# wiring_harnesses.net
KiCad netlist of a schematic drawn in EAGLE
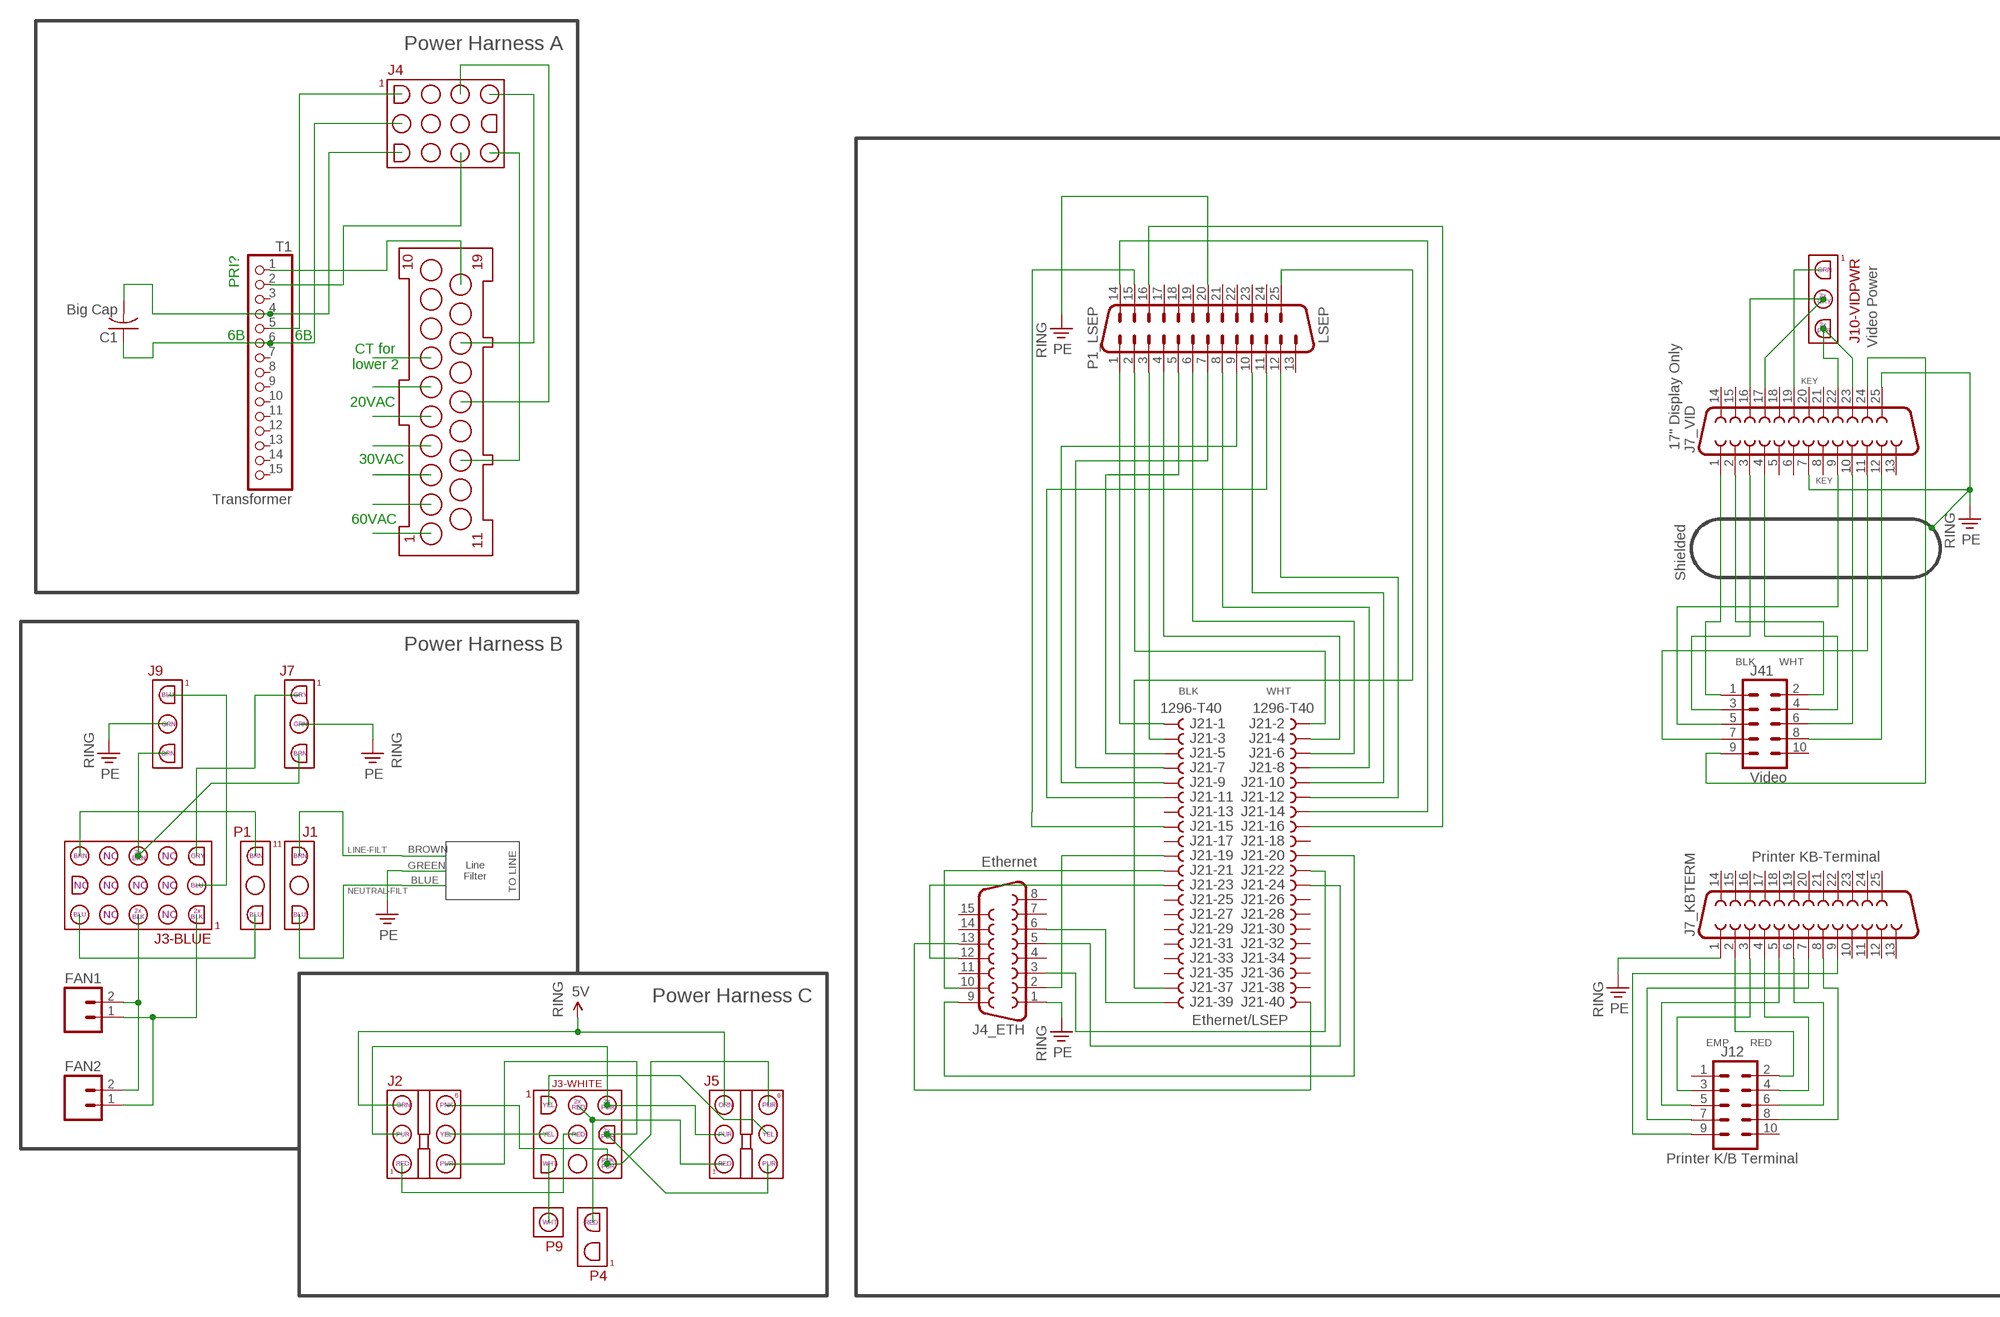
[diagram p0: schematic, sheet 1, part 1 of 2]
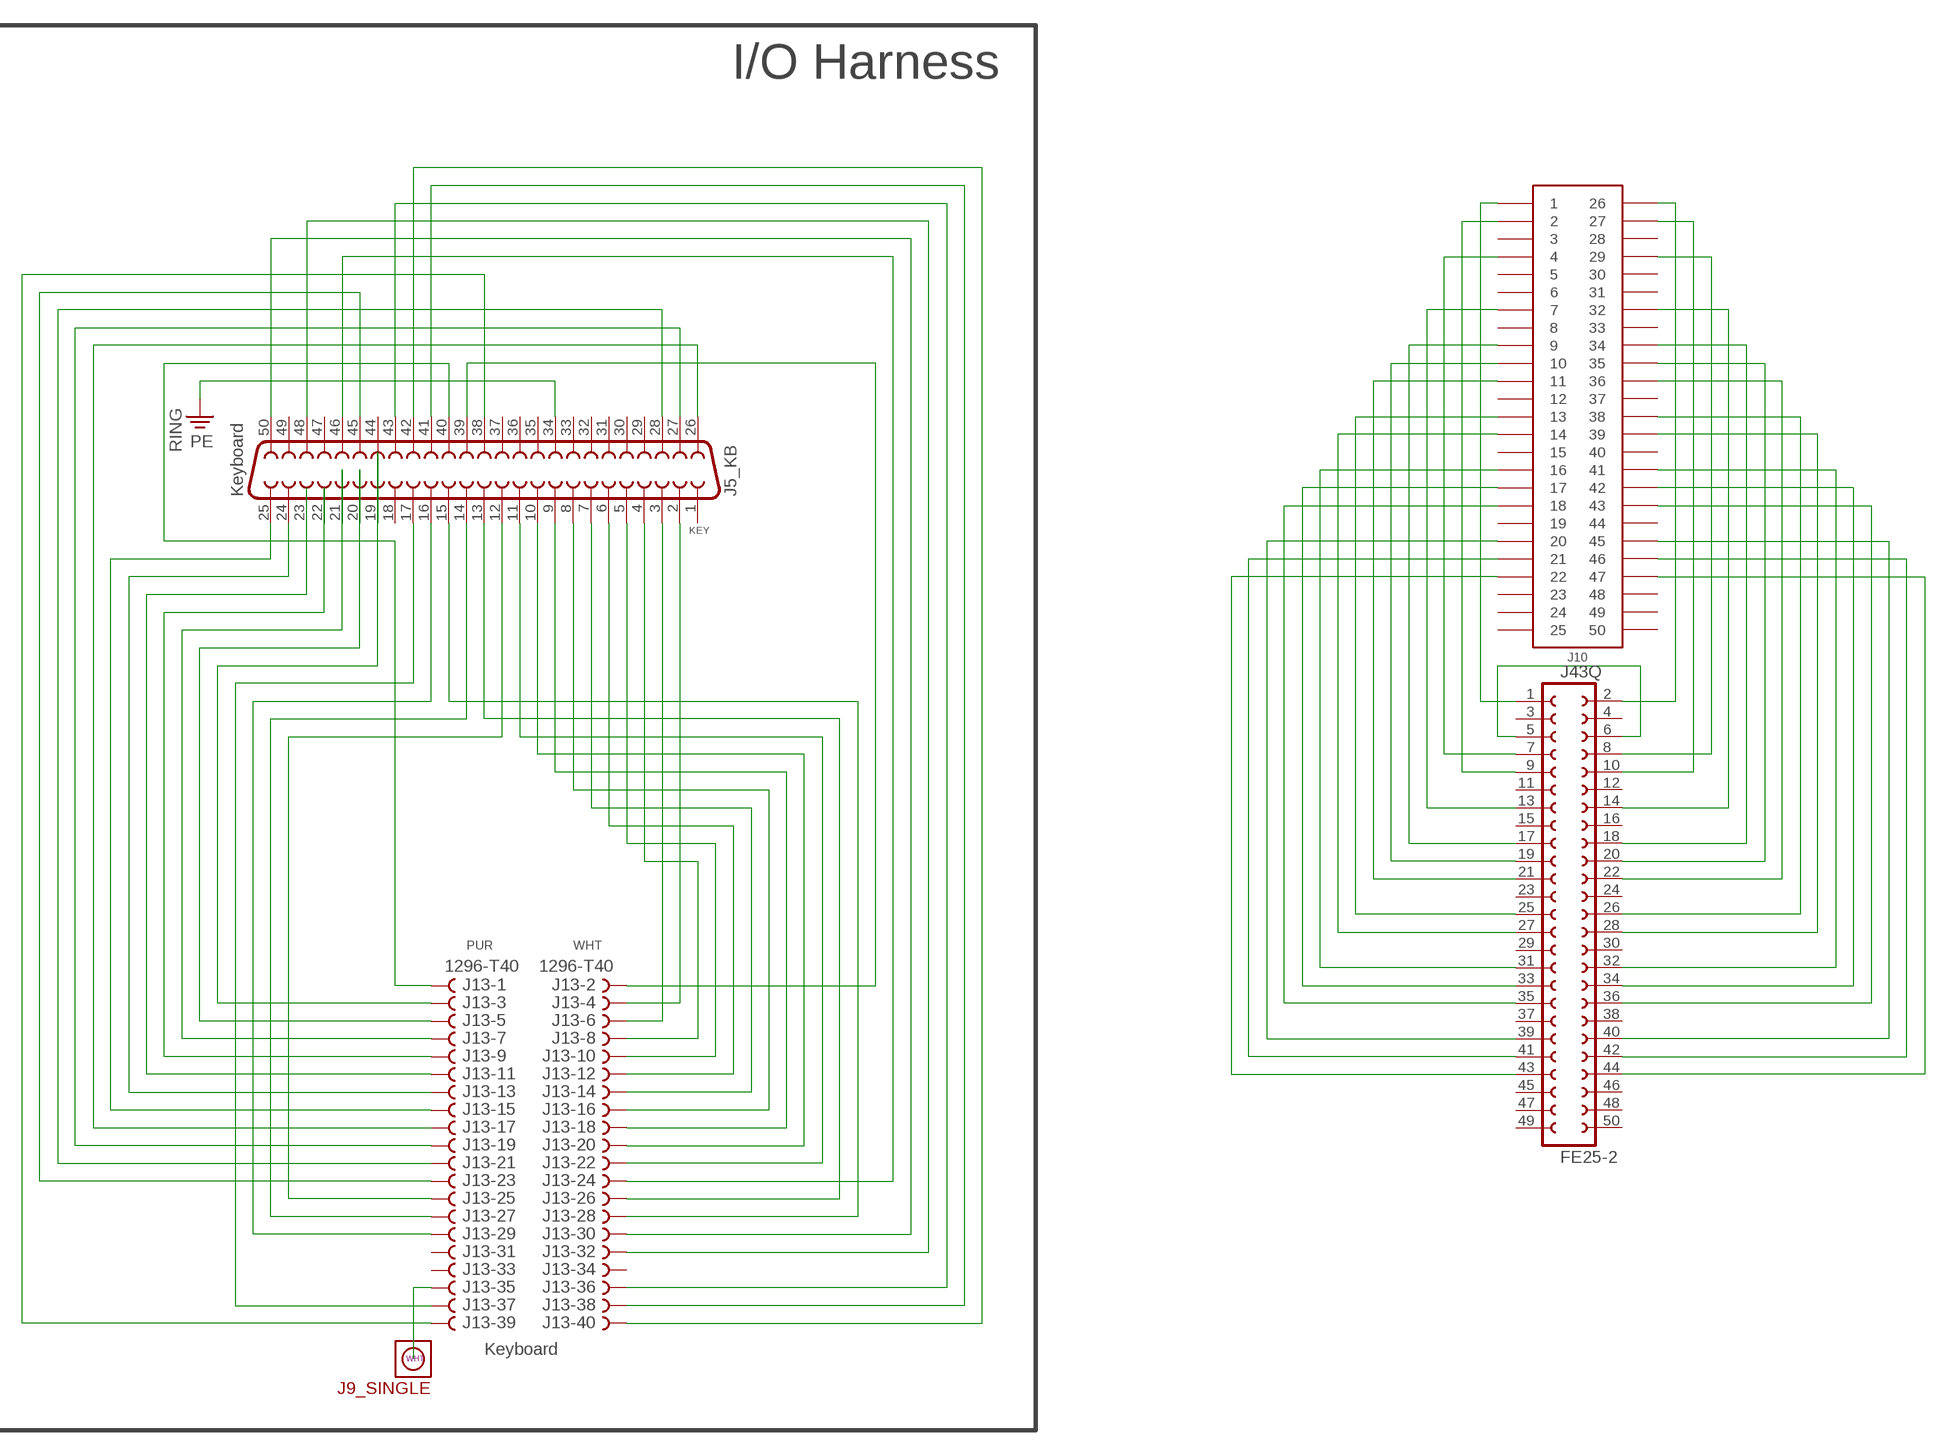
[diagram p1: schematic, sheet 1, part 2 of 2]

(export (version "E")
  (design (tool "Eeschema 10.0.6"))
  (components
    (comp (ref "C1")
      (value "Big Cap")
      (footprint "eagle-import:C275-173X316")
      (libsource (lib "eagle-import") (part "C-US275-173X316"))
    )
    (comp (ref "FAN1")
      (value "M02POGO_PIN_HOLES_ONLY")
      (footprint "eagle-import:1X02_PP_HOLES_ONLY")
      (libsource (lib "eagle-import") (part "M02POGO_PIN_HOLES_ONLY"))
    )
    (comp (ref "FAN2")
      (value "M02POGO_PIN_HOLES_ONLY")
      (footprint "eagle-import:1X02_PP_HOLES_ONLY")
      (libsource (lib "eagle-import") (part "M02POGO_PIN_HOLES_ONLY"))
    )
    (comp (ref "J1")
      (value "MOLEX-MLX3X1")
      (footprint "eagle-import:MOLEX-MLX3X1")
      (libsource (lib "eagle-import") (part "MOLEX-MLX3X1"))
    )
    (comp (ref "J2")
      (value "AMP-MATENLOK-3X2")
      (footprint "eagle-import:MATENLOK-3X2")
      (libsource (lib "eagle-import") (part "AMP-MATENLOK-3X2"))
    )
    (comp (ref "J3-BLUE")
      (value "MOLEX-MLX3X5")
      (footprint "eagle-import:MOLEX-MLX3X5")
      (libsource (lib "eagle-import") (part "MOLEX-MLX3X5"))
    )
    (comp (ref "J3-WHITE")
      (value "MOLEX-MLX3X3")
      (footprint "eagle-import:MOLEX-MLX3X3")
      (libsource (lib "eagle-import") (part "MOLEX-MLX3X3"))
    )
    (comp (ref "J4")
      (value "MOLEX-MLX3X4")
      (footprint "eagle-import:MOLEX-MLX3X4")
      (libsource (lib "eagle-import") (part "MOLEX-MLX3X4"))
    )
    (comp (ref "J4_ETH")
      (value "Ethernet")
      (footprint "eagle-import:F15D")
      (libsource (lib "eagle-import") (part "F15D"))
    )
    (comp (ref "J5")
      (value "AMP-MATENLOK-3X2")
      (footprint "eagle-import:MATENLOK-3X2")
      (libsource (lib "eagle-import") (part "AMP-MATENLOK-3X2"))
    )
    (comp (ref "J5_KB")
      (value "Keyboard")
      (footprint "eagle-import:F50VP")
      (libsource (lib "eagle-import") (part "F50VP"))
    )
    (comp (ref "J7")
      (value "MOLEX-MLX3X1")
      (footprint "eagle-import:MOLEX-MLX3X1")
      (libsource (lib "eagle-import") (part "MOLEX-MLX3X1"))
    )
    (comp (ref "J7_KBTERM")
      (value "Printer KB-Terminal")
      (footprint "eagle-import:F25VP")
      (libsource (lib "eagle-import") (part "F25VP"))
    )
    (comp (ref "J7_VID")
      (value "17\" Display Only")
      (footprint "eagle-import:F25VP")
      (libsource (lib "eagle-import") (part "F25VP"))
    )
    (comp (ref "J9")
      (value "MOLEX-MLX3X1")
      (footprint "eagle-import:MOLEX-MLX3X1")
      (libsource (lib "eagle-import") (part "MOLEX-MLX3X1"))
    )
    (comp (ref "J9_SINGLE")
      (value "MOLEX-MLX1X1")
      (footprint "eagle-import:MOLEX-MLX1X1")
      (libsource (lib "eagle-import") (part "MOLEX-MLX1X1"))
    )
    (comp (ref "J10")
      (value "EDGECON-F-0.1-50")
      (footprint "eagle-import:EDGECON-M-0.1-50")
      (libsource (lib "eagle-import") (part "EDGECON-F-0.1-50"))
    )
    (comp (ref "J10-VIDPWR")
      (value "Video Power")
      (footprint "eagle-import:MOLEX-MLX3X1")
      (libsource (lib "eagle-import") (part "MOLEX-MLX3X1"))
    )
    (comp (ref "J12")
      (value "Printer K/B Terminal")
      (footprint "eagle-import:2X5_NOSILK")
      (libsource (lib "eagle-import") (part "M05X2NO_SILK"))
    )
    (comp (ref "J13")
      (value "1296-T40")
      (footprint "eagle-import:1296-40")
      (libsource (lib "eagle-import") (part "1296-T40"))
    )
    (comp (ref "J21")
      (value "1296-T40")
      (footprint "eagle-import:1296-40")
      (libsource (lib "eagle-import") (part "1296-T40"))
    )
    (comp (ref "J41")
      (value "Video")
      (footprint "eagle-import:2X5_NOSILK")
      (libsource (lib "eagle-import") (part "M05X2NO_SILK"))
    )
    (comp (ref "J43Q")
      (value "FE25-2")
      (footprint "eagle-import:MA25-2")
      (libsource (lib "eagle-import") (part "FE25-2"))
    )
    (comp (ref "P1")
      (value "MOLEX-MLX3X1")
      (footprint "eagle-import:MOLEX-MLX3X1")
      (libsource (lib "eagle-import") (part "MOLEX-MLX3X1"))
    )
    (comp (ref "P1_LSEP")
      (value "LSEP")
      (footprint "eagle-import:M25VP")
      (libsource (lib "eagle-import") (part "DB25VP"))
    )
    (comp (ref "P4")
      (value "MOLEX-MLX2X1")
      (footprint "eagle-import:MOLEX-MLX2X1")
      (libsource (lib "eagle-import") (part "MOLEX-MLX2X1"))
    )
    (comp (ref "P9")
      (value "MOLEX-MLX1X1")
      (footprint "eagle-import:MOLEX-MLX1X1")
      (libsource (lib "eagle-import") (part "MOLEX-MLX1X1"))
    )
    (comp (ref "PSUCONN")
      (value "AMP-METRIMATE-19")
      (footprint "eagle-import:AMP-METRIMATE-19")
      (libsource (lib "eagle-import") (part "AMP-METRIMATE-19"))
    )
    (comp (ref "T1")
      (value "Transformer")
      (footprint "eagle-import:1X15")
      (libsource (lib "eagle-import") (part "PINHD-1X15"))
    )
  )
  (nets
    (net (code "1") (name "/LINE-FILT") (class "Default")
      (node (ref "J1") (pin "1") (pinfunction "1_1") (pintype "passive"))
    )
    (net (code "2") (name "/NEUTRAL-FILT") (class "Default")
      (node (ref "J1") (pin "3") (pinfunction "3_3") (pintype "passive"))
    )
    (net (code "3") (name "5V") (class "Default")
      (node (ref "J2") (pin "5") (pinfunction "5_5") (pintype "passive"))
      (node (ref "J5") (pin "5") (pinfunction "5_5") (pintype "passive"))
    )
    (net (code "4") (name "Net-(C1-Pad1)") (class "Default")
      (node (ref "C1") (pin "1") (pinfunction "1_1") (pintype "passive"))
      (node (ref "T1") (pin "6") (pinfunction "6_6") (pintype "passive"))
    )
    (net (code "5") (name "Net-(C1-Pad2)") (class "Default")
      (node (ref "C1") (pin "2") (pinfunction "2_2") (pintype "passive"))
      (node (ref "T1") (pin "4") (pinfunction "4_4") (pintype "passive"))
    )
    (net (code "6") (name "Net-(J2-Pad1)") (class "Default")
      (node (ref "J2") (pin "1") (pinfunction "1_1") (pintype "passive"))
      (node (ref "J3-WHITE") (pin "5") (pinfunction "5_5") (pintype "passive"))
    )
    (net (code "7") (name "Net-(J2-Pad2)") (class "Default")
      (node (ref "J2") (pin "2") (pinfunction "2_2") (pintype "passive"))
      (node (ref "J3-WHITE") (pin "8") (pinfunction "8_8") (pintype "passive"))
      (node (ref "J5") (pin "2") (pinfunction "2_2") (pintype "passive"))
    )
    (net (code "8") (name "Net-(J2-Pad3)") (class "Default")
      (node (ref "J2") (pin "3") (pinfunction "3_3") (pintype "passive"))
      (node (ref "J3-WHITE") (pin "7") (pinfunction "7_7") (pintype "passive"))
      (node (ref "J5") (pin "3") (pinfunction "3_3") (pintype "passive"))
    )
    (net (code "9") (name "Net-(J2-Pad4)") (class "Default")
      (node (ref "J2") (pin "4") (pinfunction "4_4") (pintype "passive"))
      (node (ref "J3-WHITE") (pin "2") (pinfunction "2_2") (pintype "passive"))
    )
    (net (code "10") (name "Net-(J2-Pad6)") (class "Default")
      (node (ref "J2") (pin "6") (pinfunction "6_6") (pintype "passive"))
      (node (ref "J3-WHITE") (pin "9") (pinfunction "9_9") (pintype "passive"))
      (node (ref "J5") (pin "6") (pinfunction "6_6") (pintype "passive"))
    )
    (net (code "11") (name "Net-(J3-BLUE-1)") (class "Default")
      (node (ref "FAN1") (pin "1") (pinfunction "1_1") (pintype "passive"))
      (node (ref "FAN2") (pin "1") (pinfunction "1_1") (pintype "passive"))
      (node (ref "J3-BLUE") (pin "15") (pinfunction "1_15") (pintype "passive"))
    )
    (net (code "12") (name "Net-(J3-BLUE-2)") (class "Default")
      (node (ref "J3-BLUE") (pin "14") (pinfunction "2_14") (pintype "passive"))
      (node (ref "J9") (pin "1") (pinfunction "1_1") (pintype "passive"))
    )
    (net (code "13") (name "Net-(J3-BLUE-3)") (class "Default")
      (node (ref "J3-BLUE") (pin "13") (pinfunction "3_13") (pintype "passive"))
      (node (ref "J7") (pin "1") (pinfunction "1_1") (pintype "passive"))
    )
    (net (code "14") (name "Net-(J3-BLUE-7)") (class "Default")
      (node (ref "FAN1") (pin "2") (pinfunction "2_2") (pintype "passive"))
      (node (ref "FAN2") (pin "2") (pinfunction "2_2") (pintype "passive"))
      (node (ref "J3-BLUE") (pin "9") (pinfunction "7_9") (pintype "passive"))
    )
    (net (code "15") (name "Net-(J3-BLUE-9)") (class "Default")
      (node (ref "J3-BLUE") (pin "7") (pinfunction "9_7") (pintype "passive"))
      (node (ref "J7") (pin "3") (pinfunction "3_3") (pintype "passive"))
      (node (ref "J9") (pin "3") (pinfunction "3_3") (pintype "passive"))
    )
    (net (code "16") (name "Net-(J3-BLUE-13)") (class "Default")
      (node (ref "J3-BLUE") (pin "3") (pinfunction "13_3") (pintype "passive"))
      (node (ref "P1") (pin "3") (pinfunction "3_3") (pintype "passive"))
    )
    (net (code "17") (name "Net-(J3-BLUE-15)") (class "Default")
      (node (ref "J3-BLUE") (pin "1") (pinfunction "15_1") (pintype "passive"))
      (node (ref "P1") (pin "1") (pinfunction "1_1") (pintype "passive"))
    )
    (net (code "18") (name "Net-(J3-WHITE-Pad1)") (class "Default")
      (node (ref "J3-WHITE") (pin "1") (pinfunction "1_1") (pintype "passive"))
      (node (ref "J5") (pin "4") (pinfunction "4_4") (pintype "passive"))
    )
    (net (code "19") (name "Net-(J3-WHITE-Pad3)") (class "Default")
      (node (ref "J3-WHITE") (pin "3") (pinfunction "3_3") (pintype "passive"))
      (node (ref "P9") (pin "1") (pinfunction "1_1") (pintype "passive"))
    )
    (net (code "20") (name "Net-(J3-WHITE-Pad4)") (class "Default")
      (node (ref "J3-WHITE") (pin "4") (pinfunction "4_4") (pintype "passive"))
      (node (ref "J5") (pin "1") (pinfunction "1_1") (pintype "passive"))
      (node (ref "P4") (pin "2") (pinfunction "2_2") (pintype "passive"))
    )
    (net (code "21") (name "Net-(J10-Pad1)") (class "Default")
      (node (ref "J10") (pin "1") (pinfunction "1_1") (pintype "bidirectional"))
      (node (ref "J43Q") (pin "1") (pinfunction "1_1") (pintype "passive"))
    )
    (net (code "22") (name "Net-(J10-Pad2)") (class "Default")
      (node (ref "J10") (pin "2") (pinfunction "2_2") (pintype "bidirectional"))
      (node (ref "J43Q") (pin "9") (pinfunction "9_9") (pintype "passive"))
    )
    (net (code "23") (name "Net-(J10-Pad4)") (class "Default")
      (node (ref "J10") (pin "4") (pinfunction "4_4") (pintype "bidirectional"))
      (node (ref "J43Q") (pin "7") (pinfunction "7_7") (pintype "passive"))
    )
    (net (code "24") (name "Net-(J10-Pad7)") (class "Default")
      (node (ref "J10") (pin "7") (pinfunction "7_7") (pintype "bidirectional"))
      (node (ref "J43Q") (pin "13") (pinfunction "13_13") (pintype "passive"))
    )
    (net (code "25") (name "Net-(J10-Pad9)") (class "Default")
      (node (ref "J10") (pin "9") (pinfunction "9_9") (pintype "bidirectional"))
      (node (ref "J43Q") (pin "17") (pinfunction "17_17") (pintype "passive"))
    )
    (net (code "26") (name "Net-(J10-Pad10)") (class "Default")
      (node (ref "J10") (pin "10") (pinfunction "10_10") (pintype "bidirectional"))
      (node (ref "J43Q") (pin "19") (pinfunction "19_19") (pintype "passive"))
    )
    (net (code "27") (name "Net-(J10-Pad11)") (class "Default")
      (node (ref "J10") (pin "11") (pinfunction "11_11") (pintype "bidirectional"))
      (node (ref "J43Q") (pin "21") (pinfunction "21_21") (pintype "passive"))
    )
    (net (code "28") (name "Net-(J10-Pad13)") (class "Default")
      (node (ref "J10") (pin "13") (pinfunction "13_13") (pintype "bidirectional"))
      (node (ref "J43Q") (pin "25") (pinfunction "25_25") (pintype "passive"))
    )
    (net (code "29") (name "Net-(J10-Pad14)") (class "Default")
      (node (ref "J10") (pin "14") (pinfunction "14_14") (pintype "bidirectional"))
      (node (ref "J43Q") (pin "27") (pinfunction "27_27") (pintype "passive"))
    )
    (net (code "30") (name "Net-(J10-Pad16)") (class "Default")
      (node (ref "J10") (pin "16") (pinfunction "16_16") (pintype "bidirectional"))
      (node (ref "J43Q") (pin "31") (pinfunction "31_31") (pintype "passive"))
    )
    (net (code "31") (name "Net-(J10-Pad17)") (class "Default")
      (node (ref "J10") (pin "17") (pinfunction "17_17") (pintype "bidirectional"))
      (node (ref "J43Q") (pin "33") (pinfunction "33_33") (pintype "passive"))
    )
    (net (code "32") (name "Net-(J10-Pad18)") (class "Default")
      (node (ref "J10") (pin "18") (pinfunction "18_18") (pintype "bidirectional"))
      (node (ref "J43Q") (pin "35") (pinfunction "35_35") (pintype "passive"))
    )
    (net (code "33") (name "Net-(J10-Pad20)") (class "Default")
      (node (ref "J10") (pin "20") (pinfunction "20_20") (pintype "bidirectional"))
      (node (ref "J43Q") (pin "39") (pinfunction "39_39") (pintype "passive"))
    )
    (net (code "34") (name "Net-(J10-Pad21)") (class "Default")
      (node (ref "J10") (pin "21") (pinfunction "21_21") (pintype "bidirectional"))
      (node (ref "J43Q") (pin "41") (pinfunction "41_41") (pintype "passive"))
    )
    (net (code "35") (name "Net-(J10-Pad22)") (class "Default")
      (node (ref "J10") (pin "22") (pinfunction "22_22") (pintype "bidirectional"))
      (node (ref "J43Q") (pin "43") (pinfunction "43_43") (pintype "passive"))
    )
    (net (code "36") (name "Net-(J10-Pad26)") (class "Default")
      (node (ref "J10") (pin "26") (pinfunction "26_26") (pintype "bidirectional"))
      (node (ref "J43Q") (pin "2") (pinfunction "2_2") (pintype "passive"))
    )
    (net (code "37") (name "Net-(J10-Pad27)") (class "Default")
      (node (ref "J10") (pin "27") (pinfunction "27_27") (pintype "bidirectional"))
      (node (ref "J43Q") (pin "10") (pinfunction "10_10") (pintype "passive"))
    )
    (net (code "38") (name "Net-(J10-Pad29)") (class "Default")
      (node (ref "J10") (pin "29") (pinfunction "29_29") (pintype "bidirectional"))
      (node (ref "J43Q") (pin "8") (pinfunction "8_8") (pintype "passive"))
    )
    (net (code "39") (name "Net-(J10-Pad32)") (class "Default")
      (node (ref "J10") (pin "32") (pinfunction "32_32") (pintype "bidirectional"))
      (node (ref "J43Q") (pin "14") (pinfunction "14_14") (pintype "passive"))
    )
    (net (code "40") (name "Net-(J10-Pad34)") (class "Default")
      (node (ref "J10") (pin "34") (pinfunction "34_34") (pintype "bidirectional"))
      (node (ref "J43Q") (pin "18") (pinfunction "18_18") (pintype "passive"))
    )
    (net (code "41") (name "Net-(J10-Pad35)") (class "Default")
      (node (ref "J10") (pin "35") (pinfunction "35_35") (pintype "bidirectional"))
      (node (ref "J43Q") (pin "20") (pinfunction "20_20") (pintype "passive"))
    )
    (net (code "42") (name "Net-(J10-Pad36)") (class "Default")
      (node (ref "J10") (pin "36") (pinfunction "36_36") (pintype "bidirectional"))
      (node (ref "J43Q") (pin "22") (pinfunction "22_22") (pintype "passive"))
    )
    (net (code "43") (name "Net-(J10-Pad38)") (class "Default")
      (node (ref "J10") (pin "38") (pinfunction "38_38") (pintype "bidirectional"))
      (node (ref "J43Q") (pin "26") (pinfunction "26_26") (pintype "passive"))
    )
    (net (code "44") (name "Net-(J10-Pad39)") (class "Default")
      (node (ref "J10") (pin "39") (pinfunction "39_39") (pintype "bidirectional"))
      (node (ref "J43Q") (pin "28") (pinfunction "28_28") (pintype "passive"))
    )
    (net (code "45") (name "Net-(J10-Pad41)") (class "Default")
      (node (ref "J10") (pin "41") (pinfunction "41_41") (pintype "bidirectional"))
      (node (ref "J43Q") (pin "32") (pinfunction "32_32") (pintype "passive"))
    )
    (net (code "46") (name "Net-(J10-Pad42)") (class "Default")
      (node (ref "J10") (pin "42") (pinfunction "42_42") (pintype "bidirectional"))
      (node (ref "J43Q") (pin "34") (pinfunction "34_34") (pintype "passive"))
    )
    (net (code "47") (name "Net-(J10-Pad43)") (class "Default")
      (node (ref "J10") (pin "43") (pinfunction "43_43") (pintype "bidirectional"))
      (node (ref "J43Q") (pin "36") (pinfunction "36_36") (pintype "passive"))
    )
    (net (code "48") (name "Net-(J10-Pad45)") (class "Default")
      (node (ref "J10") (pin "45") (pinfunction "45_45") (pintype "bidirectional"))
      (node (ref "J43Q") (pin "40") (pinfunction "40_40") (pintype "passive"))
    )
    (net (code "49") (name "Net-(J10-Pad46)") (class "Default")
      (node (ref "J10") (pin "46") (pinfunction "46_46") (pintype "bidirectional"))
      (node (ref "J43Q") (pin "42") (pinfunction "42_42") (pintype "passive"))
    )
    (net (code "50") (name "Net-(J10-Pad47)") (class "Default")
      (node (ref "J10") (pin "47") (pinfunction "47_47") (pintype "bidirectional"))
      (node (ref "J43Q") (pin "44") (pinfunction "44_44") (pintype "passive"))
    )
    (net (code "51") (name "Net-(J10-VIDPWR-Pad1)") (class "Default")
      (node (ref "J10-VIDPWR") (pin "1") (pinfunction "1_1") (pintype "passive"))
      (node (ref "J7_VID") (pin "19") (pinfunction "19_19") (pintype "passive"))
    )
    (net (code "52") (name "Net-(J10-VIDPWR-Pad2)") (class "Default")
      (node (ref "J10-VIDPWR") (pin "2") (pinfunction "2_2") (pintype "passive"))
      (node (ref "J7_VID") (pin "16") (pinfunction "16_16") (pintype "passive"))
      (node (ref "J7_VID") (pin "17") (pinfunction "17_17") (pintype "passive"))
    )
    (net (code "53") (name "Net-(J10-VIDPWR-Pad3)") (class "Default")
      (node (ref "J10-VIDPWR") (pin "3") (pinfunction "3_3") (pintype "passive"))
      (node (ref "J7_VID") (pin "22") (pinfunction "22_22") (pintype "passive"))
      (node (ref "J7_VID") (pin "23") (pinfunction "23_23") (pintype "passive"))
    )
    (net (code "54") (name "Net-(J12-Pad2)") (class "Default")
      (node (ref "J12") (pin "2") (pinfunction "2_2") (pintype "passive"))
      (node (ref "J7_KBTERM") (pin "2") (pinfunction "2_2") (pintype "passive"))
    )
    (net (code "55") (name "Net-(J12-Pad3)") (class "Default")
      (node (ref "J12") (pin "3") (pinfunction "3_3") (pintype "passive"))
      (node (ref "J7_KBTERM") (pin "3") (pinfunction "3_3") (pintype "passive"))
    )
    (net (code "56") (name "Net-(J12-Pad4)") (class "Default")
      (node (ref "J12") (pin "4") (pinfunction "4_4") (pintype "passive"))
      (node (ref "J7_KBTERM") (pin "4") (pinfunction "4_4") (pintype "passive"))
    )
    (net (code "57") (name "Net-(J12-Pad5)") (class "Default")
      (node (ref "J12") (pin "5") (pinfunction "5_5") (pintype "passive"))
      (node (ref "J7_KBTERM") (pin "5") (pinfunction "5_5") (pintype "passive"))
    )
    (net (code "58") (name "Net-(J12-Pad6)") (class "Default")
      (node (ref "J12") (pin "6") (pinfunction "6_6") (pintype "passive"))
      (node (ref "J7_KBTERM") (pin "6") (pinfunction "6_6") (pintype "passive"))
    )
    (net (code "59") (name "Net-(J12-Pad7)") (class "Default")
      (node (ref "J12") (pin "7") (pinfunction "7_7") (pintype "passive"))
      (node (ref "J7_KBTERM") (pin "7") (pinfunction "7_7") (pintype "passive"))
    )
    (net (code "60") (name "Net-(J12-Pad8)") (class "Default")
      (node (ref "J12") (pin "8") (pinfunction "8_8") (pintype "passive"))
      (node (ref "J7_KBTERM") (pin "8") (pinfunction "8_8") (pintype "passive"))
    )
    (net (code "61") (name "Net-(J12-Pad9)") (class "Default")
      (node (ref "J12") (pin "9") (pinfunction "9_9") (pintype "passive"))
      (node (ref "J7_KBTERM") (pin "9") (pinfunction "9_9") (pintype "passive"))
    )
    (net (code "62") (name "Net-(J13A-B)") (class "Default")
      (node (ref "J13") (pin "1") (pinfunction "B_1") (pintype "passive"))
      (node (ref "J5_KB") (pin "40") (pinfunction "40_40") (pintype "passive"))
    )
    (net (code "63") (name "Net-(J13AC-B)") (class "Default")
      (node (ref "J13") (pin "35") (pinfunction "B_35") (pintype "passive"))
      (node (ref "J9_SINGLE") (pin "1") (pinfunction "1_1") (pintype "passive"))
    )
    (net (code "64") (name "Net-(J13AD-B)") (class "Default")
      (node (ref "J13") (pin "36") (pinfunction "B_36") (pintype "passive"))
      (node (ref "J5_KB") (pin "43") (pinfunction "43_43") (pintype "passive"))
    )
    (net (code "65") (name "Net-(J13AE-B)") (class "Default")
      (node (ref "J13") (pin "37") (pinfunction "B_37") (pintype "passive"))
      (node (ref "J5_KB") (pin "17") (pinfunction "17_17") (pintype "passive"))
    )
    (net (code "66") (name "Net-(J13AF-B)") (class "Default")
      (node (ref "J13") (pin "38") (pinfunction "B_38") (pintype "passive"))
      (node (ref "J5_KB") (pin "41") (pinfunction "41_41") (pintype "passive"))
    )
    (net (code "67") (name "Net-(J13AG-B)") (class "Default")
      (node (ref "J13") (pin "39") (pinfunction "B_39") (pintype "passive"))
      (node (ref "J5_KB") (pin "38") (pinfunction "38_38") (pintype "passive"))
    )
    (net (code "68") (name "Net-(J13AH-B)") (class "Default")
      (node (ref "J13") (pin "4") (pinfunction "B_4") (pintype "passive"))
      (node (ref "J5_KB") (pin "2") (pinfunction "2_2") (pintype "passive"))
    )
    (net (code "69") (name "Net-(J13AI-B)") (class "Default")
      (node (ref "J13") (pin "40") (pinfunction "B_40") (pintype "passive"))
      (node (ref "J5_KB") (pin "42") (pinfunction "42_42") (pintype "passive"))
    )
    (net (code "70") (name "Net-(J13AJ-B)") (class "Default")
      (node (ref "J13") (pin "5") (pinfunction "B_5") (pintype "passive"))
      (node (ref "J5_KB") (pin "20") (pinfunction "20_20") (pintype "passive"))
    )
    (net (code "71") (name "Net-(J13AK-B)") (class "Default")
      (node (ref "J13") (pin "6") (pinfunction "B_6") (pintype "passive"))
      (node (ref "J5_KB") (pin "3") (pinfunction "3_3") (pintype "passive"))
    )
    (net (code "72") (name "Net-(J13AL-B)") (class "Default")
      (node (ref "J13") (pin "7") (pinfunction "B_7") (pintype "passive"))
      (node (ref "J5_KB") (pin "21") (pinfunction "21_21") (pintype "passive"))
    )
    (net (code "73") (name "Net-(J13AM-B)") (class "Default")
      (node (ref "J13") (pin "8") (pinfunction "B_8") (pintype "passive"))
      (node (ref "J5_KB") (pin "4") (pinfunction "4_4") (pintype "passive"))
    )
    (net (code "74") (name "Net-(J13AN-B)") (class "Default")
      (node (ref "J13") (pin "9") (pinfunction "B_9") (pintype "passive"))
      (node (ref "J5_KB") (pin "22") (pinfunction "22_22") (pintype "passive"))
    )
    (net (code "75") (name "Net-(J13B-B)") (class "Default")
      (node (ref "J13") (pin "10") (pinfunction "B_10") (pintype "passive"))
      (node (ref "J5_KB") (pin "5") (pinfunction "5_5") (pintype "passive"))
    )
    (net (code "76") (name "Net-(J13C-B)") (class "Default")
      (node (ref "J13") (pin "11") (pinfunction "B_11") (pintype "passive"))
      (node (ref "J5_KB") (pin "23") (pinfunction "23_23") (pintype "passive"))
    )
    (net (code "77") (name "Net-(J13D-B)") (class "Default")
      (node (ref "J13") (pin "12") (pinfunction "B_12") (pintype "passive"))
      (node (ref "J5_KB") (pin "6") (pinfunction "6_6") (pintype "passive"))
    )
    (net (code "78") (name "Net-(J13E-B)") (class "Default")
      (node (ref "J13") (pin "13") (pinfunction "B_13") (pintype "passive"))
      (node (ref "J5_KB") (pin "24") (pinfunction "24_24") (pintype "passive"))
    )
    (net (code "79") (name "Net-(J13F-B)") (class "Default")
      (node (ref "J13") (pin "14") (pinfunction "B_14") (pintype "passive"))
      (node (ref "J5_KB") (pin "7") (pinfunction "7_7") (pintype "passive"))
    )
    (net (code "80") (name "Net-(J13G-B)") (class "Default")
      (node (ref "J13") (pin "15") (pinfunction "B_15") (pintype "passive"))
      (node (ref "J5_KB") (pin "25") (pinfunction "25_25") (pintype "passive"))
    )
    (net (code "81") (name "Net-(J13H-B)") (class "Default")
      (node (ref "J13") (pin "16") (pinfunction "B_16") (pintype "passive"))
      (node (ref "J5_KB") (pin "8") (pinfunction "8_8") (pintype "passive"))
    )
    (net (code "82") (name "Net-(J13I-B)") (class "Default")
      (node (ref "J13") (pin "17") (pinfunction "B_17") (pintype "passive"))
      (node (ref "J5_KB") (pin "26") (pinfunction "26_26") (pintype "passive"))
    )
    (net (code "83") (name "Net-(J13J-B)") (class "Default")
      (node (ref "J13") (pin "18") (pinfunction "B_18") (pintype "passive"))
      (node (ref "J5_KB") (pin "9") (pinfunction "9_9") (pintype "passive"))
    )
    (net (code "84") (name "Net-(J13K-B)") (class "Default")
      (node (ref "J13") (pin "19") (pinfunction "B_19") (pintype "passive"))
      (node (ref "J5_KB") (pin "27") (pinfunction "27_27") (pintype "passive"))
    )
    (net (code "85") (name "Net-(J13L-B)") (class "Default")
      (node (ref "J13") (pin "2") (pinfunction "B_2") (pintype "passive"))
      (node (ref "J5_KB") (pin "39") (pinfunction "39_39") (pintype "passive"))
    )
    (net (code "86") (name "Net-(J13M-B)") (class "Default")
      (node (ref "J13") (pin "20") (pinfunction "B_20") (pintype "passive"))
      (node (ref "J5_KB") (pin "10") (pinfunction "10_10") (pintype "passive"))
    )
    (net (code "87") (name "Net-(J13N-B)") (class "Default")
      (node (ref "J13") (pin "21") (pinfunction "B_21") (pintype "passive"))
      (node (ref "J5_KB") (pin "28") (pinfunction "28_28") (pintype "passive"))
    )
    (net (code "88") (name "Net-(J13O-B)") (class "Default")
      (node (ref "J13") (pin "22") (pinfunction "B_22") (pintype "passive"))
      (node (ref "J5_KB") (pin "11") (pinfunction "11_11") (pintype "passive"))
    )
    (net (code "89") (name "Net-(J13P-B)") (class "Default")
      (node (ref "J13") (pin "23") (pinfunction "B_23") (pintype "passive"))
      (node (ref "J5_KB") (pin "45") (pinfunction "45_45") (pintype "passive"))
    )
    (net (code "90") (name "Net-(J13Q-B)") (class "Default")
      (node (ref "J13") (pin "24") (pinfunction "B_24") (pintype "passive"))
      (node (ref "J5_KB") (pin "46") (pinfunction "46_46") (pintype "passive"))
    )
    (net (code "91") (name "Net-(J13R-B)") (class "Default")
      (node (ref "J13") (pin "25") (pinfunction "B_25") (pintype "passive"))
      (node (ref "J5_KB") (pin "12") (pinfunction "12_12") (pintype "passive"))
    )
    (net (code "92") (name "Net-(J13S-B)") (class "Default")
      (node (ref "J13") (pin "26") (pinfunction "B_26") (pintype "passive"))
      (node (ref "J5_KB") (pin "13") (pinfunction "13_13") (pintype "passive"))
    )
    (net (code "93") (name "Net-(J13T-B)") (class "Default")
      (node (ref "J13") (pin "27") (pinfunction "B_27") (pintype "passive"))
      (node (ref "J5_KB") (pin "14") (pinfunction "14_14") (pintype "passive"))
    )
    (net (code "94") (name "Net-(J13U-B)") (class "Default")
      (node (ref "J13") (pin "28") (pinfunction "B_28") (pintype "passive"))
      (node (ref "J5_KB") (pin "15") (pinfunction "15_15") (pintype "passive"))
    )
    (net (code "95") (name "Net-(J13V-B)") (class "Default")
      (node (ref "J13") (pin "29") (pinfunction "B_29") (pintype "passive"))
      (node (ref "J5_KB") (pin "16") (pinfunction "16_16") (pintype "passive"))
    )
    (net (code "96") (name "Net-(J13W-B)") (class "Default")
      (node (ref "J13") (pin "3") (pinfunction "B_3") (pintype "passive"))
      (node (ref "J5_KB") (pin "19") (pinfunction "19_19") (pintype "passive"))
    )
    (net (code "97") (name "Net-(J13X-B)") (class "Default")
      (node (ref "J13") (pin "30") (pinfunction "B_30") (pintype "passive"))
      (node (ref "J5_KB") (pin "50") (pinfunction "50_50") (pintype "passive"))
    )
    (net (code "98") (name "Net-(J13Z-B)") (class "Default")
      (node (ref "J13") (pin "32") (pinfunction "B_32") (pintype "passive"))
      (node (ref "J5_KB") (pin "48") (pinfunction "48_48") (pintype "passive"))
    )
    (net (code "99") (name "Net-(J21A-B)") (class "Default")
      (node (ref "J21") (pin "1") (pinfunction "B_1") (pintype "passive"))
      (node (ref "P1_LSEP") (pin "1") (pinfunction "1_1") (pintype "passive"))
    )
    (net (code "100") (name "Net-(J21AE-B)") (class "Default")
      (node (ref "J21") (pin "37") (pinfunction "B_37") (pintype "passive"))
      (node (ref "P1_LSEP") (pin "25") (pinfunction "25_25") (pintype "passive"))
    )
    (net (code "101") (name "Net-(J21AG-B)") (class "Default")
      (node (ref "J21") (pin "39") (pinfunction "B_39") (pintype "passive"))
      (node (ref "J4_ETH") (pin "6") (pinfunction "6_6") (pintype "passive"))
    )
    (net (code "102") (name "Net-(J21AH-B)") (class "Default")
      (node (ref "J21") (pin "4") (pinfunction "B_4") (pintype "passive"))
      (node (ref "P1_LSEP") (pin "4") (pinfunction "4_4") (pintype "passive"))
    )
    (net (code "103") (name "Net-(J21AI-B)") (class "Default")
      (node (ref "J21") (pin "40") (pinfunction "B_40") (pintype "passive"))
      (node (ref "J4_ETH") (pin "13") (pinfunction "13_13") (pintype "passive"))
    )
    (net (code "104") (name "Net-(J21AJ-B)") (class "Default")
      (node (ref "J21") (pin "5") (pinfunction "B_5") (pintype "passive"))
      (node (ref "P1_LSEP") (pin "5") (pinfunction "5_5") (pintype "passive"))
    )
    (net (code "105") (name "Net-(J21AK-B)") (class "Default")
      (node (ref "J21") (pin "6") (pinfunction "B_6") (pintype "passive"))
      (node (ref "P1_LSEP") (pin "6") (pinfunction "6_6") (pintype "passive"))
    )
    (net (code "106") (name "Net-(J21AL-B)") (class "Default")
      (node (ref "J21") (pin "7") (pinfunction "B_7") (pintype "passive"))
      (node (ref "P1_LSEP") (pin "7") (pinfunction "7_7") (pintype "passive"))
    )
    (net (code "107") (name "Net-(J21AM-B)") (class "Default")
      (node (ref "J21") (pin "8") (pinfunction "B_8") (pintype "passive"))
      (node (ref "P1_LSEP") (pin "8") (pinfunction "8_8") (pintype "passive"))
    )
    (net (code "108") (name "Net-(J21AN-B)") (class "Default")
      (node (ref "J21") (pin "9") (pinfunction "B_9") (pintype "passive"))
      (node (ref "P1_LSEP") (pin "9") (pinfunction "9_9") (pintype "passive"))
    )
    (net (code "109") (name "Net-(J21B-B)") (class "Default")
      (node (ref "J21") (pin "10") (pinfunction "B_10") (pintype "passive"))
      (node (ref "P1_LSEP") (pin "10") (pinfunction "10_10") (pintype "passive"))
    )
    (net (code "110") (name "Net-(J21C-B)") (class "Default")
      (node (ref "J21") (pin "11") (pinfunction "B_11") (pintype "passive"))
      (node (ref "P1_LSEP") (pin "11") (pinfunction "11_11") (pintype "passive"))
    )
    (net (code "111") (name "Net-(J21D-B)") (class "Default")
      (node (ref "J21") (pin "12") (pinfunction "B_12") (pintype "passive"))
      (node (ref "P1_LSEP") (pin "12") (pinfunction "12_12") (pintype "passive"))
    )
    (net (code "112") (name "Net-(J21F-B)") (class "Default")
      (node (ref "J21") (pin "14") (pinfunction "B_14") (pintype "passive"))
      (node (ref "P1_LSEP") (pin "14") (pinfunction "14_14") (pintype "passive"))
    )
    (net (code "113") (name "Net-(J21G-B)") (class "Default")
      (node (ref "J21") (pin "15") (pinfunction "B_15") (pintype "passive"))
      (node (ref "P1_LSEP") (pin "15") (pinfunction "15_15") (pintype "passive"))
    )
    (net (code "114") (name "Net-(J21H-B)") (class "Default")
      (node (ref "J21") (pin "16") (pinfunction "B_16") (pintype "passive"))
      (node (ref "P1_LSEP") (pin "16") (pinfunction "16_16") (pintype "passive"))
    )
    (net (code "115") (name "Net-(J21K-B)") (class "Default")
      (node (ref "J21") (pin "19") (pinfunction "B_19") (pintype "passive"))
      (node (ref "J4_ETH") (pin "2") (pinfunction "2_2") (pintype "passive"))
    )
    (net (code "116") (name "Net-(J21L-B)") (class "Default")
      (node (ref "J21") (pin "2") (pinfunction "B_2") (pintype "passive"))
      (node (ref "P1_LSEP") (pin "2") (pinfunction "2_2") (pintype "passive"))
    )
    (net (code "117") (name "Net-(J21M-B)") (class "Default")
      (node (ref "J21") (pin "20") (pinfunction "B_20") (pintype "passive"))
      (node (ref "J4_ETH") (pin "9") (pinfunction "9_9") (pintype "passive"))
    )
    (net (code "118") (name "Net-(J21N-B)") (class "Default")
      (node (ref "J21") (pin "21") (pinfunction "B_21") (pintype "passive"))
      (node (ref "J4_ETH") (pin "10") (pinfunction "10_10") (pintype "passive"))
    )
    (net (code "119") (name "Net-(J21O-B)") (class "Default")
      (node (ref "J21") (pin "22") (pinfunction "B_22") (pintype "passive"))
      (node (ref "J4_ETH") (pin "3") (pinfunction "3_3") (pintype "passive"))
    )
    (net (code "120") (name "Net-(J21P-B)") (class "Default")
      (node (ref "J21") (pin "23") (pinfunction "B_23") (pintype "passive"))
      (node (ref "J4_ETH") (pin "12") (pinfunction "12_12") (pintype "passive"))
    )
    (net (code "121") (name "Net-(J21Q-B)") (class "Default")
      (node (ref "J21") (pin "24") (pinfunction "B_24") (pintype "passive"))
      (node (ref "J4_ETH") (pin "5") (pinfunction "5_5") (pintype "passive"))
    )
    (net (code "122") (name "Net-(J21W-B)") (class "Default")
      (node (ref "J21") (pin "3") (pinfunction "B_3") (pintype "passive"))
      (node (ref "P1_LSEP") (pin "3") (pinfunction "3_3") (pintype "passive"))
    )
    (net (code "123") (name "Net-(J41-Pad1)") (class "Default")
      (node (ref "J41") (pin "1") (pinfunction "1_1") (pintype "passive"))
      (node (ref "J7_VID") (pin "1") (pinfunction "1_1") (pintype "passive"))
    )
    (net (code "124") (name "Net-(J41-Pad2)") (class "Default")
      (node (ref "J41") (pin "2") (pinfunction "2_2") (pintype "passive"))
      (node (ref "J7_VID") (pin "2") (pinfunction "2_2") (pintype "passive"))
    )
    (net (code "125") (name "Net-(J41-Pad3)") (class "Default")
      (node (ref "J41") (pin "3") (pinfunction "3_3") (pintype "passive"))
      (node (ref "J7_VID") (pin "3") (pinfunction "3_3") (pintype "passive"))
    )
    (net (code "126") (name "Net-(J41-Pad4)") (class "Default")
      (node (ref "J41") (pin "4") (pinfunction "4_4") (pintype "passive"))
      (node (ref "J7_VID") (pin "4") (pinfunction "4_4") (pintype "passive"))
    )
    (net (code "127") (name "Net-(J41-Pad5)") (class "Default")
      (node (ref "J41") (pin "5") (pinfunction "5_5") (pintype "passive"))
      (node (ref "J7_VID") (pin "9") (pinfunction "9_9") (pintype "passive"))
    )
    (net (code "128") (name "Net-(J41-Pad6)") (class "Default")
      (node (ref "J41") (pin "6") (pinfunction "6_6") (pintype "passive"))
      (node (ref "J7_VID") (pin "10") (pinfunction "10_10") (pintype "passive"))
    )
    (net (code "129") (name "Net-(J41-Pad7)") (class "Default")
      (node (ref "J41") (pin "7") (pinfunction "7_7") (pintype "passive"))
      (node (ref "J7_VID") (pin "11") (pinfunction "11_11") (pintype "passive"))
    )
    (net (code "130") (name "Net-(J41-Pad8)") (class "Default")
      (node (ref "J41") (pin "8") (pinfunction "8_8") (pintype "passive"))
      (node (ref "J7_VID") (pin "12") (pinfunction "12_12") (pintype "passive"))
    )
    (net (code "131") (name "Net-(J41-Pad9)") (class "Default")
      (node (ref "J41") (pin "9") (pinfunction "9_9") (pintype "passive"))
      (node (ref "J7_VID") (pin "24") (pinfunction "24_24") (pintype "passive"))
    )
    (net (code "132") (name "Net-(J43Q-Pad5)") (class "Default")
      (node (ref "J43Q") (pin "5") (pinfunction "5_5") (pintype "passive"))
      (node (ref "J43Q") (pin "6") (pinfunction "6_6") (pintype "passive"))
    )
    (net (code "133") (name "Net-(PSUCONN-Pad19)") (class "Default")
      (node (ref "PSUCONN") (pin "19") (pinfunction "19_19") (pintype "bidirectional"))
      (node (ref "T1") (pin "1") (pinfunction "1_1") (pintype "passive"))
    )
    (net (code "134") (name "PE") (class "Default")
      (node (ref "J4_ETH") (pin "1") (pinfunction "1_1") (pintype "passive"))
      (node (ref "J5_KB") (pin "34") (pinfunction "34_34") (pintype "passive"))
      (node (ref "J7") (pin "2") (pinfunction "2_2") (pintype "passive"))
      (node (ref "J7_KBTERM") (pin "1") (pinfunction "1_1") (pintype "passive"))
      (node (ref "J7_VID") (pin "25") (pinfunction "25_25") (pintype "passive"))
      (node (ref "J7_VID") (pin "7") (pinfunction "7_7") (pintype "passive"))
      (node (ref "J9") (pin "2") (pinfunction "2_2") (pintype "passive"))
      (node (ref "P1_LSEP") (pin "20") (pinfunction "20_20") (pintype "passive"))
    )
    (net (code "135") (name "unconnected-(J1-Pad2)") (class "Default")
      (node (ref "J1") (pin "2") (pinfunction "2_2") (pintype "passive"))
    )
    (net (code "136") (name "unconnected-(J3-BLUE-4-Pad12)") (class "Default")
      (node (ref "J3-BLUE") (pin "12") (pinfunction "4_12") (pintype "passive"))
    )
    (net (code "137") (name "unconnected-(J3-BLUE-5-Pad11)") (class "Default")
      (node (ref "J3-BLUE") (pin "11") (pinfunction "5_11") (pintype "passive"))
    )
    (net (code "138") (name "unconnected-(J3-BLUE-6-Pad10)") (class "Default")
      (node (ref "J3-BLUE") (pin "10") (pinfunction "6_10") (pintype "passive"))
    )
    (net (code "139") (name "unconnected-(J3-BLUE-10-Pad6)") (class "Default")
      (node (ref "J3-BLUE") (pin "6") (pinfunction "10_6") (pintype "passive"))
    )
    (net (code "140") (name "unconnected-(J3-BLUE-11-Pad5)") (class "Default")
      (node (ref "J3-BLUE") (pin "5") (pinfunction "11_5") (pintype "passive"))
    )
    (net (code "141") (name "unconnected-(J3-BLUE-12-Pad4)") (class "Default")
      (node (ref "J3-BLUE") (pin "4") (pinfunction "12_4") (pintype "passive"))
    )
    (net (code "142") (name "unconnected-(J3-BLUE-14-Pad2)") (class "Default")
      (node (ref "J3-BLUE") (pin "2") (pinfunction "14_2") (pintype "passive"))
    )
    (net (code "143") (name "unconnected-(J3-BLUE-Pad8)") (class "Default")
      (node (ref "J3-BLUE") (pin "8") (pinfunction "8_8") (pintype "passive"))
    )
    (net (code "144") (name "unconnected-(J3-WHITE-Pad6)") (class "Default")
      (node (ref "J3-WHITE") (pin "6") (pinfunction "6_6") (pintype "passive"))
    )
    (net (code "145") (name "unconnected-(J4-1-Pad12)") (class "Default")
      (node (ref "J4") (pin "12") (pinfunction "1_12") (pintype "passive"))
    )
    (net (code "146") (name "unconnected-(J4-2-Pad11)") (class "Default")
      (node (ref "J4") (pin "11") (pinfunction "2_11") (pintype "passive"))
    )
    (net (code "147") (name "unconnected-(J4-3-Pad10)") (class "Default")
      (node (ref "J4") (pin "10") (pinfunction "3_10") (pintype "passive"))
    )
    (net (code "148") (name "unconnected-(J4-4-Pad9)") (class "Default")
      (node (ref "J4") (pin "9") (pinfunction "4_9") (pintype "passive"))
    )
    (net (code "149") (name "unconnected-(J4-5-Pad8)") (class "Default")
      (node (ref "J4") (pin "8") (pinfunction "5_8") (pintype "passive"))
    )
    (net (code "150") (name "unconnected-(J4-6-Pad7)") (class "Default")
      (node (ref "J4") (pin "7") (pinfunction "6_7") (pintype "passive"))
    )
    (net (code "151") (name "unconnected-(J4-7-Pad6)") (class "Default")
      (node (ref "J4") (pin "6") (pinfunction "7_6") (pintype "passive"))
    )
    (net (code "152") (name "unconnected-(J4-8-Pad5)") (class "Default")
      (node (ref "J4") (pin "5") (pinfunction "8_5") (pintype "passive"))
    )
    (net (code "153") (name "unconnected-(J4-9-Pad4)") (class "Default")
      (node (ref "J4") (pin "4") (pinfunction "9_4") (pintype "passive"))
    )
    (net (code "154") (name "unconnected-(J4-10-Pad3)") (class "Default")
      (node (ref "J4") (pin "3") (pinfunction "10_3") (pintype "passive"))
    )
    (net (code "155") (name "unconnected-(J4-11-Pad2)") (class "Default")
      (node (ref "J4") (pin "2") (pinfunction "11_2") (pintype "passive"))
    )
    (net (code "156") (name "unconnected-(J4-12-Pad1)") (class "Default")
      (node (ref "J4") (pin "1") (pinfunction "12_1") (pintype "passive"))
    )
    (net (code "157") (name "unconnected-(J4_ETH-Pad4)") (class "Default")
      (node (ref "J4_ETH") (pin "4") (pinfunction "4_4") (pintype "passive"))
    )
    (net (code "158") (name "unconnected-(J4_ETH-Pad7)") (class "Default")
      (node (ref "J4_ETH") (pin "7") (pinfunction "7_7") (pintype "passive"))
    )
    (net (code "159") (name "unconnected-(J4_ETH-Pad8)") (class "Default")
      (node (ref "J4_ETH") (pin "8") (pinfunction "8_8") (pintype "passive"))
    )
    (net (code "160") (name "unconnected-(J4_ETH-Pad11)") (class "Default")
      (node (ref "J4_ETH") (pin "11") (pinfunction "11_11") (pintype "passive"))
    )
    (net (code "161") (name "unconnected-(J4_ETH-Pad14)") (class "Default")
      (node (ref "J4_ETH") (pin "14") (pinfunction "14_14") (pintype "passive"))
    )
    (net (code "162") (name "unconnected-(J4_ETH-Pad15)") (class "Default")
      (node (ref "J4_ETH") (pin "15") (pinfunction "15_15") (pintype "passive"))
    )
    (net (code "163") (name "unconnected-(J5_KB-Pad1)") (class "Default")
      (node (ref "J5_KB") (pin "1") (pinfunction "1_1") (pintype "passive"))
    )
    (net (code "164") (name "unconnected-(J5_KB-Pad18)") (class "Default")
      (node (ref "J5_KB") (pin "18") (pinfunction "18_18") (pintype "passive"))
    )
    (net (code "165") (name "unconnected-(J5_KB-Pad29)") (class "Default")
      (node (ref "J5_KB") (pin "29") (pinfunction "29_29") (pintype "passive"))
    )
    (net (code "166") (name "unconnected-(J5_KB-Pad30)") (class "Default")
      (node (ref "J5_KB") (pin "30") (pinfunction "30_30") (pintype "passive"))
    )
    (net (code "167") (name "unconnected-(J5_KB-Pad31)") (class "Default")
      (node (ref "J5_KB") (pin "31") (pinfunction "31_31") (pintype "passive"))
    )
    (net (code "168") (name "unconnected-(J5_KB-Pad32)") (class "Default")
      (node (ref "J5_KB") (pin "32") (pinfunction "32_32") (pintype "passive"))
    )
    (net (code "169") (name "unconnected-(J5_KB-Pad33)") (class "Default")
      (node (ref "J5_KB") (pin "33") (pinfunction "33_33") (pintype "passive"))
    )
    (net (code "170") (name "unconnected-(J5_KB-Pad35)") (class "Default")
      (node (ref "J5_KB") (pin "35") (pinfunction "35_35") (pintype "passive"))
    )
    (net (code "171") (name "unconnected-(J5_KB-Pad36)") (class "Default")
      (node (ref "J5_KB") (pin "36") (pinfunction "36_36") (pintype "passive"))
    )
    (net (code "172") (name "unconnected-(J5_KB-Pad37)") (class "Default")
      (node (ref "J5_KB") (pin "37") (pinfunction "37_37") (pintype "passive"))
    )
    (net (code "173") (name "unconnected-(J5_KB-Pad44)") (class "Default")
      (node (ref "J5_KB") (pin "44") (pinfunction "44_44") (pintype "passive"))
    )
    (net (code "174") (name "unconnected-(J5_KB-Pad47)") (class "Default")
      (node (ref "J5_KB") (pin "47") (pinfunction "47_47") (pintype "passive"))
    )
    (net (code "175") (name "unconnected-(J5_KB-Pad49)") (class "Default")
      (node (ref "J5_KB") (pin "49") (pinfunction "49_49") (pintype "passive"))
    )
    (net (code "176") (name "unconnected-(J7_KBTERM-Pad10)") (class "Default")
      (node (ref "J7_KBTERM") (pin "10") (pinfunction "10_10") (pintype "passive"))
    )
    (net (code "177") (name "unconnected-(J7_KBTERM-Pad11)") (class "Default")
      (node (ref "J7_KBTERM") (pin "11") (pinfunction "11_11") (pintype "passive"))
    )
    (net (code "178") (name "unconnected-(J7_KBTERM-Pad12)") (class "Default")
      (node (ref "J7_KBTERM") (pin "12") (pinfunction "12_12") (pintype "passive"))
    )
    (net (code "179") (name "unconnected-(J7_KBTERM-Pad13)") (class "Default")
      (node (ref "J7_KBTERM") (pin "13") (pinfunction "13_13") (pintype "passive"))
    )
    (net (code "180") (name "unconnected-(J7_KBTERM-Pad14)") (class "Default")
      (node (ref "J7_KBTERM") (pin "14") (pinfunction "14_14") (pintype "passive"))
    )
    (net (code "181") (name "unconnected-(J7_KBTERM-Pad15)") (class "Default")
      (node (ref "J7_KBTERM") (pin "15") (pinfunction "15_15") (pintype "passive"))
    )
    (net (code "182") (name "unconnected-(J7_KBTERM-Pad16)") (class "Default")
      (node (ref "J7_KBTERM") (pin "16") (pinfunction "16_16") (pintype "passive"))
    )
    (net (code "183") (name "unconnected-(J7_KBTERM-Pad17)") (class "Default")
      (node (ref "J7_KBTERM") (pin "17") (pinfunction "17_17") (pintype "passive"))
    )
    (net (code "184") (name "unconnected-(J7_KBTERM-Pad18)") (class "Default")
      (node (ref "J7_KBTERM") (pin "18") (pinfunction "18_18") (pintype "passive"))
    )
    (net (code "185") (name "unconnected-(J7_KBTERM-Pad19)") (class "Default")
      (node (ref "J7_KBTERM") (pin "19") (pinfunction "19_19") (pintype "passive"))
    )
    (net (code "186") (name "unconnected-(J7_KBTERM-Pad20)") (class "Default")
      (node (ref "J7_KBTERM") (pin "20") (pinfunction "20_20") (pintype "passive"))
    )
    (net (code "187") (name "unconnected-(J7_KBTERM-Pad21)") (class "Default")
      (node (ref "J7_KBTERM") (pin "21") (pinfunction "21_21") (pintype "passive"))
    )
    (net (code "188") (name "unconnected-(J7_KBTERM-Pad22)") (class "Default")
      (node (ref "J7_KBTERM") (pin "22") (pinfunction "22_22") (pintype "passive"))
    )
    (net (code "189") (name "unconnected-(J7_KBTERM-Pad23)") (class "Default")
      (node (ref "J7_KBTERM") (pin "23") (pinfunction "23_23") (pintype "passive"))
    )
    (net (code "190") (name "unconnected-(J7_KBTERM-Pad24)") (class "Default")
      (node (ref "J7_KBTERM") (pin "24") (pinfunction "24_24") (pintype "passive"))
    )
    (net (code "191") (name "unconnected-(J7_KBTERM-Pad25)") (class "Default")
      (node (ref "J7_KBTERM") (pin "25") (pinfunction "25_25") (pintype "passive"))
    )
    (net (code "192") (name "unconnected-(J7_VID-Pad5)") (class "Default")
      (node (ref "J7_VID") (pin "5") (pinfunction "5_5") (pintype "passive"))
    )
    (net (code "193") (name "unconnected-(J7_VID-Pad6)") (class "Default")
      (node (ref "J7_VID") (pin "6") (pinfunction "6_6") (pintype "passive"))
    )
    (net (code "194") (name "unconnected-(J7_VID-Pad8)") (class "Default")
      (node (ref "J7_VID") (pin "8") (pinfunction "8_8") (pintype "passive"))
    )
    (net (code "195") (name "unconnected-(J7_VID-Pad13)") (class "Default")
      (node (ref "J7_VID") (pin "13") (pinfunction "13_13") (pintype "passive"))
    )
    (net (code "196") (name "unconnected-(J7_VID-Pad14)") (class "Default")
      (node (ref "J7_VID") (pin "14") (pinfunction "14_14") (pintype "passive"))
    )
    (net (code "197") (name "unconnected-(J7_VID-Pad15)") (class "Default")
      (node (ref "J7_VID") (pin "15") (pinfunction "15_15") (pintype "passive"))
    )
    (net (code "198") (name "unconnected-(J7_VID-Pad18)") (class "Default")
      (node (ref "J7_VID") (pin "18") (pinfunction "18_18") (pintype "passive"))
    )
    (net (code "199") (name "unconnected-(J7_VID-Pad20)") (class "Default")
      (node (ref "J7_VID") (pin "20") (pinfunction "20_20") (pintype "passive"))
    )
    (net (code "200") (name "unconnected-(J7_VID-Pad21)") (class "Default")
      (node (ref "J7_VID") (pin "21") (pinfunction "21_21") (pintype "passive"))
    )
    (net (code "201") (name "unconnected-(J10-Pad3)") (class "Default")
      (node (ref "J10") (pin "3") (pinfunction "3_3") (pintype "bidirectional"))
    )
    (net (code "202") (name "unconnected-(J10-Pad5)") (class "Default")
      (node (ref "J10") (pin "5") (pinfunction "5_5") (pintype "bidirectional"))
    )
    (net (code "203") (name "unconnected-(J10-Pad6)") (class "Default")
      (node (ref "J10") (pin "6") (pinfunction "6_6") (pintype "bidirectional"))
    )
    (net (code "204") (name "unconnected-(J10-Pad8)") (class "Default")
      (node (ref "J10") (pin "8") (pinfunction "8_8") (pintype "bidirectional"))
    )
    (net (code "205") (name "unconnected-(J10-Pad12)") (class "Default")
      (node (ref "J10") (pin "12") (pinfunction "12_12") (pintype "bidirectional"))
    )
    (net (code "206") (name "unconnected-(J10-Pad15)") (class "Default")
      (node (ref "J10") (pin "15") (pinfunction "15_15") (pintype "bidirectional"))
    )
    (net (code "207") (name "unconnected-(J10-Pad19)") (class "Default")
      (node (ref "J10") (pin "19") (pinfunction "19_19") (pintype "bidirectional"))
    )
    (net (code "208") (name "unconnected-(J10-Pad23)") (class "Default")
      (node (ref "J10") (pin "23") (pinfunction "23_23") (pintype "bidirectional"))
    )
    (net (code "209") (name "unconnected-(J10-Pad24)") (class "Default")
      (node (ref "J10") (pin "24") (pinfunction "24_24") (pintype "bidirectional"))
    )
    (net (code "210") (name "unconnected-(J10-Pad25)") (class "Default")
      (node (ref "J10") (pin "25") (pinfunction "25_25") (pintype "bidirectional"))
    )
    (net (code "211") (name "unconnected-(J10-Pad28)") (class "Default")
      (node (ref "J10") (pin "28") (pinfunction "28_28") (pintype "bidirectional"))
    )
    (net (code "212") (name "unconnected-(J10-Pad30)") (class "Default")
      (node (ref "J10") (pin "30") (pinfunction "30_30") (pintype "bidirectional"))
    )
    (net (code "213") (name "unconnected-(J10-Pad31)") (class "Default")
      (node (ref "J10") (pin "31") (pinfunction "31_31") (pintype "bidirectional"))
    )
    (net (code "214") (name "unconnected-(J10-Pad33)") (class "Default")
      (node (ref "J10") (pin "33") (pinfunction "33_33") (pintype "bidirectional"))
    )
    (net (code "215") (name "unconnected-(J10-Pad37)") (class "Default")
      (node (ref "J10") (pin "37") (pinfunction "37_37") (pintype "bidirectional"))
    )
    (net (code "216") (name "unconnected-(J10-Pad40)") (class "Default")
      (node (ref "J10") (pin "40") (pinfunction "40_40") (pintype "bidirectional"))
    )
    (net (code "217") (name "unconnected-(J10-Pad44)") (class "Default")
      (node (ref "J10") (pin "44") (pinfunction "44_44") (pintype "bidirectional"))
    )
    (net (code "218") (name "unconnected-(J10-Pad48)") (class "Default")
      (node (ref "J10") (pin "48") (pinfunction "48_48") (pintype "bidirectional"))
    )
    (net (code "219") (name "unconnected-(J10-Pad49)") (class "Default")
      (node (ref "J10") (pin "49") (pinfunction "49_49") (pintype "bidirectional"))
    )
    (net (code "220") (name "unconnected-(J10-Pad50)") (class "Default")
      (node (ref "J10") (pin "50") (pinfunction "50_50") (pintype "bidirectional"))
    )
    (net (code "221") (name "unconnected-(J12-Pad1)") (class "Default")
      (node (ref "J12") (pin "1") (pinfunction "1_1") (pintype "passive"))
    )
    (net (code "222") (name "unconnected-(J12-Pad10)") (class "Default")
      (node (ref "J12") (pin "10") (pinfunction "10_10") (pintype "passive"))
    )
    (net (code "223") (name "unconnected-(J13AA-B-Pad33)") (class "Default")
      (node (ref "J13") (pin "33") (pinfunction "B_33") (pintype "passive"))
    )
    (net (code "224") (name "unconnected-(J13AB-B-Pad34)") (class "Default")
      (node (ref "J13") (pin "34") (pinfunction "B_34") (pintype "passive"))
    )
    (net (code "225") (name "unconnected-(J13Y-B-Pad31)") (class "Default")
      (node (ref "J13") (pin "31") (pinfunction "B_31") (pintype "passive"))
    )
    (net (code "226") (name "unconnected-(J21AA-B-Pad33)") (class "Default")
      (node (ref "J21") (pin "33") (pinfunction "B_33") (pintype "passive"))
    )
    (net (code "227") (name "unconnected-(J21AB-B-Pad34)") (class "Default")
      (node (ref "J21") (pin "34") (pinfunction "B_34") (pintype "passive"))
    )
    (net (code "228") (name "unconnected-(J21AC-B-Pad35)") (class "Default")
      (node (ref "J21") (pin "35") (pinfunction "B_35") (pintype "passive"))
    )
    (net (code "229") (name "unconnected-(J21AD-B-Pad36)") (class "Default")
      (node (ref "J21") (pin "36") (pinfunction "B_36") (pintype "passive"))
    )
    (net (code "230") (name "unconnected-(J21AF-B-Pad38)") (class "Default")
      (node (ref "J21") (pin "38") (pinfunction "B_38") (pintype "passive"))
    )
    (net (code "231") (name "unconnected-(J21E-B-Pad13)") (class "Default")
      (node (ref "J21") (pin "13") (pinfunction "B_13") (pintype "passive"))
    )
    (net (code "232") (name "unconnected-(J21I-B-Pad17)") (class "Default")
      (node (ref "J21") (pin "17") (pinfunction "B_17") (pintype "passive"))
    )
    (net (code "233") (name "unconnected-(J21J-B-Pad18)") (class "Default")
      (node (ref "J21") (pin "18") (pinfunction "B_18") (pintype "passive"))
    )
    (net (code "234") (name "unconnected-(J21R-B-Pad25)") (class "Default")
      (node (ref "J21") (pin "25") (pinfunction "B_25") (pintype "passive"))
    )
    (net (code "235") (name "unconnected-(J21S-B-Pad26)") (class "Default")
      (node (ref "J21") (pin "26") (pinfunction "B_26") (pintype "passive"))
    )
    (net (code "236") (name "unconnected-(J21T-B-Pad27)") (class "Default")
      (node (ref "J21") (pin "27") (pinfunction "B_27") (pintype "passive"))
    )
    (net (code "237") (name "unconnected-(J21U-B-Pad28)") (class "Default")
      (node (ref "J21") (pin "28") (pinfunction "B_28") (pintype "passive"))
    )
    (net (code "238") (name "unconnected-(J21V-B-Pad29)") (class "Default")
      (node (ref "J21") (pin "29") (pinfunction "B_29") (pintype "passive"))
    )
    (net (code "239") (name "unconnected-(J21X-B-Pad30)") (class "Default")
      (node (ref "J21") (pin "30") (pinfunction "B_30") (pintype "passive"))
    )
    (net (code "240") (name "unconnected-(J21Y-B-Pad31)") (class "Default")
      (node (ref "J21") (pin "31") (pinfunction "B_31") (pintype "passive"))
    )
    (net (code "241") (name "unconnected-(J21Z-B-Pad32)") (class "Default")
      (node (ref "J21") (pin "32") (pinfunction "B_32") (pintype "passive"))
    )
    (net (code "242") (name "unconnected-(J41-Pad10)") (class "Default")
      (node (ref "J41") (pin "10") (pinfunction "10_10") (pintype "passive"))
    )
    (net (code "243") (name "unconnected-(J43Q-Pad3)") (class "Default")
      (node (ref "J43Q") (pin "3") (pinfunction "3_3") (pintype "passive"))
    )
    (net (code "244") (name "unconnected-(J43Q-Pad4)") (class "Default")
      (node (ref "J43Q") (pin "4") (pinfunction "4_4") (pintype "passive"))
    )
    (net (code "245") (name "unconnected-(J43Q-Pad11)") (class "Default")
      (node (ref "J43Q") (pin "11") (pinfunction "11_11") (pintype "passive"))
    )
    (net (code "246") (name "unconnected-(J43Q-Pad12)") (class "Default")
      (node (ref "J43Q") (pin "12") (pinfunction "12_12") (pintype "passive"))
    )
    (net (code "247") (name "unconnected-(J43Q-Pad15)") (class "Default")
      (node (ref "J43Q") (pin "15") (pinfunction "15_15") (pintype "passive"))
    )
    (net (code "248") (name "unconnected-(J43Q-Pad16)") (class "Default")
      (node (ref "J43Q") (pin "16") (pinfunction "16_16") (pintype "passive"))
    )
    (net (code "249") (name "unconnected-(J43Q-Pad23)") (class "Default")
      (node (ref "J43Q") (pin "23") (pinfunction "23_23") (pintype "passive"))
    )
    (net (code "250") (name "unconnected-(J43Q-Pad24)") (class "Default")
      (node (ref "J43Q") (pin "24") (pinfunction "24_24") (pintype "passive"))
    )
    (net (code "251") (name "unconnected-(J43Q-Pad29)") (class "Default")
      (node (ref "J43Q") (pin "29") (pinfunction "29_29") (pintype "passive"))
    )
    (net (code "252") (name "unconnected-(J43Q-Pad30)") (class "Default")
      (node (ref "J43Q") (pin "30") (pinfunction "30_30") (pintype "passive"))
    )
    (net (code "253") (name "unconnected-(J43Q-Pad37)") (class "Default")
      (node (ref "J43Q") (pin "37") (pinfunction "37_37") (pintype "passive"))
    )
    (net (code "254") (name "unconnected-(J43Q-Pad38)") (class "Default")
      (node (ref "J43Q") (pin "38") (pinfunction "38_38") (pintype "passive"))
    )
    (net (code "255") (name "unconnected-(J43Q-Pad45)") (class "Default")
      (node (ref "J43Q") (pin "45") (pinfunction "45_45") (pintype "passive"))
    )
    (net (code "256") (name "unconnected-(J43Q-Pad46)") (class "Default")
      (node (ref "J43Q") (pin "46") (pinfunction "46_46") (pintype "passive"))
    )
    (net (code "257") (name "unconnected-(J43Q-Pad47)") (class "Default")
      (node (ref "J43Q") (pin "47") (pinfunction "47_47") (pintype "passive"))
    )
    (net (code "258") (name "unconnected-(J43Q-Pad48)") (class "Default")
      (node (ref "J43Q") (pin "48") (pinfunction "48_48") (pintype "passive"))
    )
    (net (code "259") (name "unconnected-(J43Q-Pad49)") (class "Default")
      (node (ref "J43Q") (pin "49") (pinfunction "49_49") (pintype "passive"))
    )
    (net (code "260") (name "unconnected-(J43Q-Pad50)") (class "Default")
      (node (ref "J43Q") (pin "50") (pinfunction "50_50") (pintype "passive"))
    )
    (net (code "261") (name "unconnected-(P1-Pad2)") (class "Default")
      (node (ref "P1") (pin "2") (pinfunction "2_2") (pintype "passive"))
    )
    (net (code "262") (name "unconnected-(P1_LSEP-Pad13)") (class "Default")
      (node (ref "P1_LSEP") (pin "13") (pinfunction "13_13") (pintype "passive"))
    )
    (net (code "263") (name "unconnected-(P1_LSEP-Pad17)") (class "Default")
      (node (ref "P1_LSEP") (pin "17") (pinfunction "17_17") (pintype "passive"))
    )
    (net (code "264") (name "unconnected-(P1_LSEP-Pad18)") (class "Default")
      (node (ref "P1_LSEP") (pin "18") (pinfunction "18_18") (pintype "passive"))
    )
    (net (code "265") (name "unconnected-(P1_LSEP-Pad19)") (class "Default")
      (node (ref "P1_LSEP") (pin "19") (pinfunction "19_19") (pintype "passive"))
    )
    (net (code "266") (name "unconnected-(P1_LSEP-Pad21)") (class "Default")
      (node (ref "P1_LSEP") (pin "21") (pinfunction "21_21") (pintype "passive"))
    )
    (net (code "267") (name "unconnected-(P1_LSEP-Pad22)") (class "Default")
      (node (ref "P1_LSEP") (pin "22") (pinfunction "22_22") (pintype "passive"))
    )
    (net (code "268") (name "unconnected-(P1_LSEP-Pad23)") (class "Default")
      (node (ref "P1_LSEP") (pin "23") (pinfunction "23_23") (pintype "passive"))
    )
    (net (code "269") (name "unconnected-(P1_LSEP-Pad24)") (class "Default")
      (node (ref "P1_LSEP") (pin "24") (pinfunction "24_24") (pintype "passive"))
    )
    (net (code "270") (name "unconnected-(P4-Pad1)") (class "Default")
      (node (ref "P4") (pin "1") (pinfunction "1_1") (pintype "passive"))
    )
    (net (code "271") (name "unconnected-(PSUCONN-Pad1)") (class "Default")
      (node (ref "PSUCONN") (pin "1") (pinfunction "1_1") (pintype "bidirectional"))
    )
    (net (code "272") (name "unconnected-(PSUCONN-Pad2)") (class "Default")
      (node (ref "PSUCONN") (pin "2") (pinfunction "2_2") (pintype "bidirectional"))
    )
    (net (code "273") (name "unconnected-(PSUCONN-Pad3)") (class "Default")
      (node (ref "PSUCONN") (pin "3") (pinfunction "3_3") (pintype "bidirectional"))
    )
    (net (code "274") (name "unconnected-(PSUCONN-Pad4)") (class "Default")
      (node (ref "PSUCONN") (pin "4") (pinfunction "4_4") (pintype "bidirectional"))
    )
    (net (code "275") (name "unconnected-(PSUCONN-Pad5)") (class "Default")
      (node (ref "PSUCONN") (pin "5") (pinfunction "5_5") (pintype "bidirectional"))
    )
    (net (code "276") (name "unconnected-(PSUCONN-Pad6)") (class "Default")
      (node (ref "PSUCONN") (pin "6") (pinfunction "6_6") (pintype "bidirectional"))
    )
    (net (code "277") (name "unconnected-(PSUCONN-Pad7)") (class "Default")
      (node (ref "PSUCONN") (pin "7") (pinfunction "7_7") (pintype "bidirectional"))
    )
    (net (code "278") (name "unconnected-(PSUCONN-Pad8)") (class "Default")
      (node (ref "PSUCONN") (pin "8") (pinfunction "8_8") (pintype "bidirectional"))
    )
    (net (code "279") (name "unconnected-(PSUCONN-Pad9)") (class "Default")
      (node (ref "PSUCONN") (pin "9") (pinfunction "9_9") (pintype "bidirectional"))
    )
    (net (code "280") (name "unconnected-(PSUCONN-Pad10)") (class "Default")
      (node (ref "PSUCONN") (pin "10") (pinfunction "10_10") (pintype "bidirectional"))
    )
    (net (code "281") (name "unconnected-(PSUCONN-Pad11)") (class "Default")
      (node (ref "PSUCONN") (pin "11") (pinfunction "11_11") (pintype "bidirectional"))
    )
    (net (code "282") (name "unconnected-(PSUCONN-Pad12)") (class "Default")
      (node (ref "PSUCONN") (pin "12") (pinfunction "12_12") (pintype "bidirectional"))
    )
    (net (code "283") (name "unconnected-(PSUCONN-Pad13)") (class "Default")
      (node (ref "PSUCONN") (pin "13") (pinfunction "13_13") (pintype "bidirectional"))
    )
    (net (code "284") (name "unconnected-(PSUCONN-Pad14)") (class "Default")
      (node (ref "PSUCONN") (pin "14") (pinfunction "14_14") (pintype "bidirectional"))
    )
    (net (code "285") (name "unconnected-(PSUCONN-Pad15)") (class "Default")
      (node (ref "PSUCONN") (pin "15") (pinfunction "15_15") (pintype "bidirectional"))
    )
    (net (code "286") (name "unconnected-(PSUCONN-Pad16)") (class "Default")
      (node (ref "PSUCONN") (pin "16") (pinfunction "16_16") (pintype "bidirectional"))
    )
    (net (code "287") (name "unconnected-(PSUCONN-Pad17)") (class "Default")
      (node (ref "PSUCONN") (pin "17") (pinfunction "17_17") (pintype "bidirectional"))
    )
    (net (code "288") (name "unconnected-(PSUCONN-Pad18)") (class "Default")
      (node (ref "PSUCONN") (pin "18") (pinfunction "18_18") (pintype "bidirectional"))
    )
    (net (code "289") (name "unconnected-(T1-Pad2)") (class "Default")
      (node (ref "T1") (pin "2") (pinfunction "2_2") (pintype "passive"))
    )
    (net (code "290") (name "unconnected-(T1-Pad3)") (class "Default")
      (node (ref "T1") (pin "3") (pinfunction "3_3") (pintype "passive"))
    )
    (net (code "291") (name "unconnected-(T1-Pad5)") (class "Default")
      (node (ref "T1") (pin "5") (pinfunction "5_5") (pintype "passive"))
    )
    (net (code "292") (name "unconnected-(T1-Pad7)") (class "Default")
      (node (ref "T1") (pin "7") (pinfunction "7_7") (pintype "passive"))
    )
    (net (code "293") (name "unconnected-(T1-Pad8)") (class "Default")
      (node (ref "T1") (pin "8") (pinfunction "8_8") (pintype "passive"))
    )
    (net (code "294") (name "unconnected-(T1-Pad9)") (class "Default")
      (node (ref "T1") (pin "9") (pinfunction "9_9") (pintype "passive"))
    )
    (net (code "295") (name "unconnected-(T1-Pad10)") (class "Default")
      (node (ref "T1") (pin "10") (pinfunction "10_10") (pintype "passive"))
    )
    (net (code "296") (name "unconnected-(T1-Pad11)") (class "Default")
      (node (ref "T1") (pin "11") (pinfunction "11_11") (pintype "passive"))
    )
    (net (code "297") (name "unconnected-(T1-Pad12)") (class "Default")
      (node (ref "T1") (pin "12") (pinfunction "12_12") (pintype "passive"))
    )
    (net (code "298") (name "unconnected-(T1-Pad13)") (class "Default")
      (node (ref "T1") (pin "13") (pinfunction "13_13") (pintype "passive"))
    )
    (net (code "299") (name "unconnected-(T1-Pad14)") (class "Default")
      (node (ref "T1") (pin "14") (pinfunction "14_14") (pintype "passive"))
    )
    (net (code "300") (name "unconnected-(T1-Pad15)") (class "Default")
      (node (ref "T1") (pin "15") (pinfunction "15_15") (pintype "passive"))
    )
  )
)
